# V1.net
KiCad netlist of a schematic drawn in EAGLE
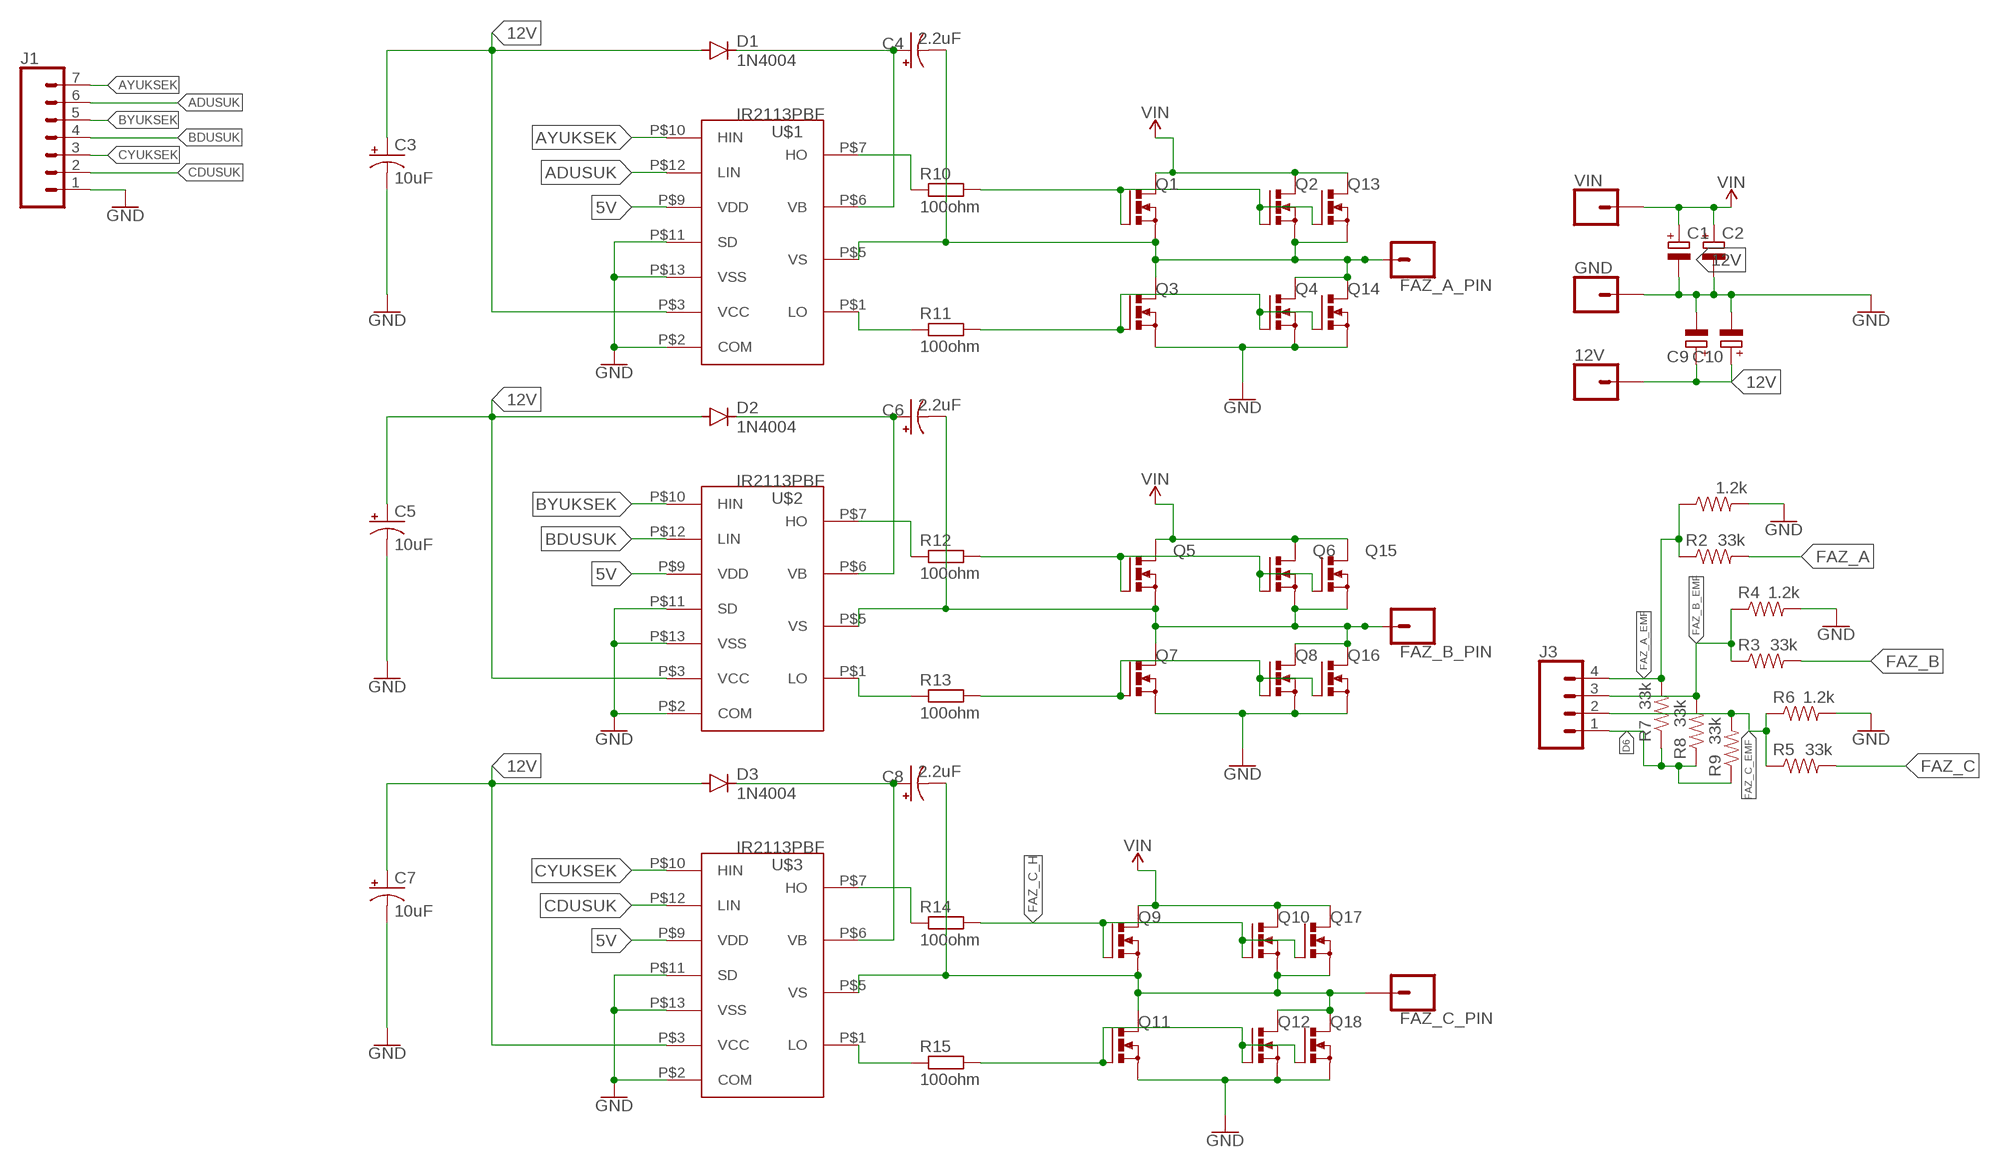
[diagram p0: schematic, sheet 1]

(export (version "E")
  (design (tool "Eeschema 10.0.6"))
  (components
    (comp (ref "12V")
      (value "CONN_01SNAP-MALE")
      (footprint "eagle-import:SNAP-MALE")
      (libsource (lib "eagle-import") (part "CONN_01SNAP-MALE"))
    )
    (comp (ref "C1")
      (value "C-POL_RADIAL-25MM-DIA")
      (footprint "eagle-import:CAPPRD550W110D1250H2500B")
      (libsource (lib "eagle-import") (part "C-POLRADIAL-25MM-DIA_"))
    )
    (comp (ref "C2")
      (value "C-POL_RADIAL-25MM-DIA")
      (footprint "eagle-import:CAPPRD550W110D1250H2500B")
      (libsource (lib "eagle-import") (part "C-POLRADIAL-25MM-DIA_"))
    )
    (comp (ref "C3")
      (value "10uF")
      (footprint "eagle-import:CPOL-RADIAL-2.5MM-5MM")
      (libsource (lib "eagle-import") (part "10UF-POLAR-RADIAL-2.5MM-25V-20%"))
    )
    (comp (ref "C4")
      (value "2.2uF")
      (footprint "eagle-import:CPOL-RADIAL-2.5MM-5MM")
      (libsource (lib "eagle-import") (part "10UF-POLAR-RADIAL-2.5MM-25V-20%"))
    )
    (comp (ref "C5")
      (value "10uF")
      (footprint "eagle-import:CPOL-RADIAL-2.5MM-5MM")
      (libsource (lib "eagle-import") (part "10UF-POLAR-RADIAL-2.5MM-25V-20%"))
    )
    (comp (ref "C6")
      (value "2.2uF")
      (footprint "eagle-import:CPOL-RADIAL-2.5MM-5MM")
      (libsource (lib "eagle-import") (part "10UF-POLAR-RADIAL-2.5MM-25V-20%"))
    )
    (comp (ref "C7")
      (value "10uF")
      (footprint "eagle-import:CPOL-RADIAL-2.5MM-5MM")
      (libsource (lib "eagle-import") (part "10UF-POLAR-RADIAL-2.5MM-25V-20%"))
    )
    (comp (ref "C8")
      (value "2.2uF")
      (footprint "eagle-import:CPOL-RADIAL-2.5MM-5MM")
      (libsource (lib "eagle-import") (part "10UF-POLAR-RADIAL-2.5MM-25V-20%"))
    )
    (comp (ref "C9")
      (value "C-POL_RADIAL-25MM-DIA")
      (footprint "eagle-import:CAPPRD550W110D1250H2500B")
      (libsource (lib "eagle-import") (part "C-POLRADIAL-25MM-DIA_"))
    )
    (comp (ref "C10")
      (value "C-POL_RADIAL-25MM-DIA")
      (footprint "eagle-import:CAPPRD550W110D1250H2500B")
      (libsource (lib "eagle-import") (part "C-POLRADIAL-25MM-DIA_"))
    )
    (comp (ref "D1")
      (value "1N4004")
      (footprint "eagle-import:DO41-10")
      (libsource (lib "eagle-import") (part "1N4004"))
    )
    (comp (ref "D2")
      (value "1N4004")
      (footprint "eagle-import:DO41-10")
      (libsource (lib "eagle-import") (part "1N4004"))
    )
    (comp (ref "D3")
      (value "1N4004")
      (footprint "eagle-import:DO41-10")
      (libsource (lib "eagle-import") (part "1N4004"))
    )
    (comp (ref "FAZ_A_PIN")
      (value "CONN_01SNAP-MALE")
      (footprint "eagle-import:SNAP-MALE")
      (libsource (lib "eagle-import") (part "CONN_01SNAP-MALE"))
    )
    (comp (ref "FAZ_B_PIN")
      (value "CONN_01SNAP-MALE")
      (footprint "eagle-import:SNAP-MALE")
      (libsource (lib "eagle-import") (part "CONN_01SNAP-MALE"))
    )
    (comp (ref "FAZ_C_PIN")
      (value "CONN_01SNAP-MALE")
      (footprint "eagle-import:SNAP-MALE")
      (libsource (lib "eagle-import") (part "CONN_01SNAP-MALE"))
    )
    (comp (ref "GND")
      (value "CONN_01SNAP-MALE")
      (footprint "eagle-import:SNAP-MALE")
      (libsource (lib "eagle-import") (part "CONN_01SNAP-MALE"))
    )
    (comp (ref "J1")
      (value "CONN_07")
      (footprint "eagle-import:1X07")
      (libsource (lib "eagle-import") (part "CONN_07"))
    )
    (comp (ref "J3")
      (value "CONN_04")
      (footprint "eagle-import:1X04")
      (libsource (lib "eagle-import") (part "CONN_04"))
    )
    (comp (ref "Q1")
      (value "PMOSFET_NTO220BV")
      (footprint "eagle-import:TO220BV")
      (libsource (lib "eagle-import") (part "PMOSFET_NTO220BV"))
    )
    (comp (ref "Q2")
      (value "PMOSFET_NTO220BV")
      (footprint "eagle-import:TO220BV")
      (libsource (lib "eagle-import") (part "PMOSFET_NTO220BV"))
    )
    (comp (ref "Q3")
      (value "PMOSFET_NTO220BV")
      (footprint "eagle-import:TO220BV")
      (libsource (lib "eagle-import") (part "PMOSFET_NTO220BV"))
    )
    (comp (ref "Q4")
      (value "PMOSFET_NTO220BV")
      (footprint "eagle-import:TO220BV")
      (libsource (lib "eagle-import") (part "PMOSFET_NTO220BV"))
    )
    (comp (ref "Q5")
      (value "PMOSFET_NTO220BV")
      (footprint "eagle-import:TO220BV")
      (libsource (lib "eagle-import") (part "PMOSFET_NTO220BV"))
    )
    (comp (ref "Q6")
      (value "PMOSFET_NTO220BV")
      (footprint "eagle-import:TO220BV")
      (libsource (lib "eagle-import") (part "PMOSFET_NTO220BV"))
    )
    (comp (ref "Q7")
      (value "PMOSFET_NTO220BV")
      (footprint "eagle-import:TO220BV")
      (libsource (lib "eagle-import") (part "PMOSFET_NTO220BV"))
    )
    (comp (ref "Q8")
      (value "PMOSFET_NTO220BV")
      (footprint "eagle-import:TO220BV")
      (libsource (lib "eagle-import") (part "PMOSFET_NTO220BV"))
    )
    (comp (ref "Q9")
      (value "PMOSFET_NTO220BV")
      (footprint "eagle-import:TO220BV")
      (libsource (lib "eagle-import") (part "PMOSFET_NTO220BV"))
    )
    (comp (ref "Q10")
      (value "PMOSFET_NTO220BV")
      (footprint "eagle-import:TO220BV")
      (libsource (lib "eagle-import") (part "PMOSFET_NTO220BV"))
    )
    (comp (ref "Q11")
      (value "PMOSFET_NTO220BV")
      (footprint "eagle-import:TO220BV")
      (libsource (lib "eagle-import") (part "PMOSFET_NTO220BV"))
    )
    (comp (ref "Q12")
      (value "PMOSFET_NTO220BV")
      (footprint "eagle-import:TO220BV")
      (libsource (lib "eagle-import") (part "PMOSFET_NTO220BV"))
    )
    (comp (ref "Q13")
      (value "PMOSFET_NTO220BV")
      (footprint "eagle-import:TO220BV")
      (libsource (lib "eagle-import") (part "PMOSFET_NTO220BV"))
    )
    (comp (ref "Q14")
      (value "PMOSFET_NTO220BV")
      (footprint "eagle-import:TO220BV")
      (libsource (lib "eagle-import") (part "PMOSFET_NTO220BV"))
    )
    (comp (ref "Q15")
      (value "PMOSFET_NTO220BV")
      (footprint "eagle-import:TO220BV")
      (libsource (lib "eagle-import") (part "PMOSFET_NTO220BV"))
    )
    (comp (ref "Q16")
      (value "PMOSFET_NTO220BV")
      (footprint "eagle-import:TO220BV")
      (libsource (lib "eagle-import") (part "PMOSFET_NTO220BV"))
    )
    (comp (ref "Q17")
      (value "PMOSFET_NTO220BV")
      (footprint "eagle-import:TO220BV")
      (libsource (lib "eagle-import") (part "PMOSFET_NTO220BV"))
    )
    (comp (ref "Q18")
      (value "PMOSFET_NTO220BV")
      (footprint "eagle-import:TO220BV")
      (libsource (lib "eagle-import") (part "PMOSFET_NTO220BV"))
    )
    (comp (ref "R1")
      (value "1.2k")
      (footprint "eagle-import:AXIAL-0.3")
      (libsource (lib "eagle-import") (part "15KOHM-HORIZ-1/4W-5%"))
    )
    (comp (ref "R2")
      (value "33k")
      (footprint "eagle-import:AXIAL-0.3")
      (libsource (lib "eagle-import") (part "15KOHM-HORIZ-1/4W-5%"))
    )
    (comp (ref "R3")
      (value "33k")
      (footprint "eagle-import:AXIAL-0.3")
      (libsource (lib "eagle-import") (part "15KOHM-HORIZ-1/4W-5%"))
    )
    (comp (ref "R4")
      (value "1.2k")
      (footprint "eagle-import:AXIAL-0.3")
      (libsource (lib "eagle-import") (part "15KOHM-HORIZ-1/4W-5%"))
    )
    (comp (ref "R5")
      (value "33k")
      (footprint "eagle-import:AXIAL-0.3")
      (libsource (lib "eagle-import") (part "15KOHM-HORIZ-1/4W-5%"))
    )
    (comp (ref "R6")
      (value "1.2k")
      (footprint "eagle-import:AXIAL-0.3")
      (libsource (lib "eagle-import") (part "15KOHM-HORIZ-1/4W-5%"))
    )
    (comp (ref "R7")
      (value "33k")
      (footprint "eagle-import:AXIAL-0.3")
      (libsource (lib "eagle-import") (part "15KOHM-HORIZ-1/4W-5%"))
    )
    (comp (ref "R8")
      (value "33k")
      (footprint "eagle-import:AXIAL-0.3")
      (libsource (lib "eagle-import") (part "15KOHM-HORIZ-1/4W-5%"))
    )
    (comp (ref "R9")
      (value "33k")
      (footprint "eagle-import:AXIAL-0.3")
      (libsource (lib "eagle-import") (part "15KOHM-HORIZ-1/4W-5%"))
    )
    (comp (ref "R10")
      (value "100ohm")
      (footprint "eagle-import:0207_10")
      (libsource (lib "eagle-import") (part "R-EU_0207/10"))
    )
    (comp (ref "R11")
      (value "100ohm")
      (footprint "eagle-import:0207_10")
      (libsource (lib "eagle-import") (part "R-EU_0207/10"))
    )
    (comp (ref "R12")
      (value "100ohm")
      (footprint "eagle-import:0207_10")
      (libsource (lib "eagle-import") (part "R-EU_0207/10"))
    )
    (comp (ref "R13")
      (value "100ohm")
      (footprint "eagle-import:0207_10")
      (libsource (lib "eagle-import") (part "R-EU_0207/10"))
    )
    (comp (ref "R14")
      (value "100ohm")
      (footprint "eagle-import:0207_10")
      (libsource (lib "eagle-import") (part "R-EU_0207/10"))
    )
    (comp (ref "R15")
      (value "100ohm")
      (footprint "eagle-import:0207_10")
      (libsource (lib "eagle-import") (part "R-EU_0207/10"))
    )
    (comp (ref "U$1")
      (value "IR2113PBF")
      (footprint "eagle-import:PDIP-14")
      (libsource (lib "eagle-import") (part "IR2113PBF"))
    )
    (comp (ref "U$2")
      (value "IR2113PBF")
      (footprint "eagle-import:PDIP-14")
      (libsource (lib "eagle-import") (part "IR2113PBF"))
    )
    (comp (ref "U$3")
      (value "IR2113PBF")
      (footprint "eagle-import:PDIP-14")
      (libsource (lib "eagle-import") (part "IR2113PBF"))
    )
    (comp (ref "VIN")
      (value "CONN_01SNAP-MALE")
      (footprint "eagle-import:SNAP-MALE")
      (libsource (lib "eagle-import") (part "CONN_01SNAP-MALE"))
    )
  )
  (nets
    (net (code "1") (name "5V") (class "Default")
      (node (ref "U$1") (pin "P$9") (pinfunction "VDD_P$9") (pintype "bidirectional"))
      (node (ref "U$2") (pin "P$9") (pinfunction "VDD_P$9") (pintype "bidirectional"))
      (node (ref "U$3") (pin "P$9") (pinfunction "VDD_P$9") (pintype "bidirectional"))
    )
    (net (code "2") (name "12V") (class "Default")
      (node (ref "12V") (pin "2") (pinfunction "1_2") (pintype "passive"))
      (node (ref "C10") (pin "1") (pinfunction "+_1") (pintype "passive"))
      (node (ref "C3") (pin "1") (pinfunction "+_1") (pintype "passive"))
      (node (ref "C5") (pin "1") (pinfunction "+_1") (pintype "passive"))
      (node (ref "C7") (pin "1") (pinfunction "+_1") (pintype "passive"))
      (node (ref "C9") (pin "1") (pinfunction "+_1") (pintype "passive"))
      (node (ref "D1") (pin "A") (pinfunction "A_A") (pintype "passive"))
      (node (ref "D2") (pin "A") (pinfunction "A_A") (pintype "passive"))
      (node (ref "D3") (pin "A") (pinfunction "A_A") (pintype "passive"))
      (node (ref "U$1") (pin "P$3") (pinfunction "VCC_P$3") (pintype "bidirectional"))
      (node (ref "U$2") (pin "P$3") (pinfunction "VCC_P$3") (pintype "bidirectional"))
      (node (ref "U$3") (pin "P$3") (pinfunction "VCC_P$3") (pintype "bidirectional"))
    )
    (net (code "3") (name "ADUSUK") (class "Default")
      (node (ref "J1") (pin "6") (pinfunction "6_6") (pintype "passive"))
      (node (ref "U$1") (pin "P$12") (pinfunction "LIN_P$12") (pintype "bidirectional"))
    )
    (net (code "4") (name "AYUKSEK") (class "Default")
      (node (ref "J1") (pin "7") (pinfunction "7_7") (pintype "passive"))
      (node (ref "U$1") (pin "P$10") (pinfunction "HIN_P$10") (pintype "bidirectional"))
    )
    (net (code "5") (name "BDUSUK") (class "Default")
      (node (ref "J1") (pin "4") (pinfunction "4_4") (pintype "passive"))
      (node (ref "U$2") (pin "P$12") (pinfunction "LIN_P$12") (pintype "bidirectional"))
    )
    (net (code "6") (name "BYUKSEK") (class "Default")
      (node (ref "J1") (pin "5") (pinfunction "5_5") (pintype "passive"))
      (node (ref "U$2") (pin "P$10") (pinfunction "HIN_P$10") (pintype "bidirectional"))
    )
    (net (code "7") (name "CDUSUK") (class "Default")
      (node (ref "J1") (pin "2") (pinfunction "2_2") (pintype "passive"))
      (node (ref "U$3") (pin "P$12") (pinfunction "LIN_P$12") (pintype "bidirectional"))
    )
    (net (code "8") (name "CYUKSEK") (class "Default")
      (node (ref "J1") (pin "3") (pinfunction "3_3") (pintype "passive"))
      (node (ref "U$3") (pin "P$10") (pinfunction "HIN_P$10") (pintype "bidirectional"))
    )
    (net (code "9") (name "D6") (class "Default")
      (node (ref "J3") (pin "1") (pinfunction "1_1") (pintype "passive"))
      (node (ref "R7") (pin "P$1") (pinfunction "1_P$1") (pintype "passive"))
      (node (ref "R8") (pin "P$1") (pinfunction "1_P$1") (pintype "passive"))
      (node (ref "R9") (pin "P$1") (pinfunction "1_P$1") (pintype "passive"))
    )
    (net (code "10") (name "FAZ_A") (class "Default")
      (node (ref "C4") (pin "2") (pinfunction "-_2") (pintype "passive"))
      (node (ref "FAZ_A_PIN") (pin "2") (pinfunction "1_2") (pintype "passive"))
      (node (ref "Q1") (pin "S") (pinfunction "S_S") (pintype "passive"))
      (node (ref "Q13") (pin "S") (pinfunction "S_S") (pintype "passive"))
      (node (ref "Q14") (pin "D") (pinfunction "D_D") (pintype "passive"))
      (node (ref "Q2") (pin "S") (pinfunction "S_S") (pintype "passive"))
      (node (ref "Q3") (pin "D") (pinfunction "D_D") (pintype "passive"))
      (node (ref "Q4") (pin "D") (pinfunction "D_D") (pintype "passive"))
      (node (ref "R2") (pin "P$2") (pinfunction "2_P$2") (pintype "passive"))
      (node (ref "U$1") (pin "P$5") (pinfunction "VS_P$5") (pintype "bidirectional"))
    )
    (net (code "11") (name "FAZ_A_EMF") (class "Default")
      (node (ref "J3") (pin "4") (pinfunction "4_4") (pintype "passive"))
      (node (ref "R1") (pin "P$1") (pinfunction "1_P$1") (pintype "passive"))
      (node (ref "R2") (pin "P$1") (pinfunction "1_P$1") (pintype "passive"))
      (node (ref "R7") (pin "P$2") (pinfunction "2_P$2") (pintype "passive"))
    )
    (net (code "12") (name "FAZ_B") (class "Default")
      (node (ref "C6") (pin "2") (pinfunction "-_2") (pintype "passive"))
      (node (ref "FAZ_B_PIN") (pin "2") (pinfunction "1_2") (pintype "passive"))
      (node (ref "Q15") (pin "S") (pinfunction "S_S") (pintype "passive"))
      (node (ref "Q16") (pin "D") (pinfunction "D_D") (pintype "passive"))
      (node (ref "Q5") (pin "S") (pinfunction "S_S") (pintype "passive"))
      (node (ref "Q6") (pin "S") (pinfunction "S_S") (pintype "passive"))
      (node (ref "Q7") (pin "D") (pinfunction "D_D") (pintype "passive"))
      (node (ref "Q8") (pin "D") (pinfunction "D_D") (pintype "passive"))
      (node (ref "R3") (pin "P$2") (pinfunction "2_P$2") (pintype "passive"))
      (node (ref "U$2") (pin "P$5") (pinfunction "VS_P$5") (pintype "bidirectional"))
    )
    (net (code "13") (name "FAZ_B_EMF") (class "Default")
      (node (ref "J3") (pin "3") (pinfunction "3_3") (pintype "passive"))
      (node (ref "R3") (pin "P$1") (pinfunction "1_P$1") (pintype "passive"))
      (node (ref "R4") (pin "P$1") (pinfunction "1_P$1") (pintype "passive"))
      (node (ref "R8") (pin "P$2") (pinfunction "2_P$2") (pintype "passive"))
    )
    (net (code "14") (name "FAZ_C") (class "Default")
      (node (ref "C8") (pin "2") (pinfunction "-_2") (pintype "passive"))
      (node (ref "FAZ_C_PIN") (pin "2") (pinfunction "1_2") (pintype "passive"))
      (node (ref "Q10") (pin "S") (pinfunction "S_S") (pintype "passive"))
      (node (ref "Q11") (pin "D") (pinfunction "D_D") (pintype "passive"))
      (node (ref "Q12") (pin "D") (pinfunction "D_D") (pintype "passive"))
      (node (ref "Q17") (pin "S") (pinfunction "S_S") (pintype "passive"))
      (node (ref "Q18") (pin "D") (pinfunction "D_D") (pintype "passive"))
      (node (ref "Q9") (pin "S") (pinfunction "S_S") (pintype "passive"))
      (node (ref "R5") (pin "P$2") (pinfunction "2_P$2") (pintype "passive"))
      (node (ref "U$3") (pin "P$5") (pinfunction "VS_P$5") (pintype "bidirectional"))
    )
    (net (code "15") (name "FAZ_C_EMF") (class "Default")
      (node (ref "J3") (pin "2") (pinfunction "2_2") (pintype "passive"))
      (node (ref "R5") (pin "P$1") (pinfunction "1_P$1") (pintype "passive"))
      (node (ref "R6") (pin "P$1") (pinfunction "1_P$1") (pintype "passive"))
      (node (ref "R9") (pin "P$2") (pinfunction "2_P$2") (pintype "passive"))
    )
    (net (code "16") (name "FAZ_C_H") (class "Default")
      (node (ref "Q10") (pin "G") (pinfunction "G_G") (pintype "passive"))
      (node (ref "Q17") (pin "G") (pinfunction "G_G") (pintype "passive"))
      (node (ref "Q9") (pin "G") (pinfunction "G_G") (pintype "passive"))
      (node (ref "R14") (pin "2") (pinfunction "2_2") (pintype "passive"))
    )
    (net (code "17") (name "GND") (class "Default")
      (node (ref "C1") (pin "2") (pinfunction "-_2") (pintype "passive"))
      (node (ref "C10") (pin "2") (pinfunction "-_2") (pintype "passive"))
      (node (ref "C2") (pin "2") (pinfunction "-_2") (pintype "passive"))
      (node (ref "C3") (pin "2") (pinfunction "-_2") (pintype "passive"))
      (node (ref "C5") (pin "2") (pinfunction "-_2") (pintype "passive"))
      (node (ref "C7") (pin "2") (pinfunction "-_2") (pintype "passive"))
      (node (ref "C9") (pin "2") (pinfunction "-_2") (pintype "passive"))
      (node (ref "GND") (pin "2") (pinfunction "1_2") (pintype "passive"))
      (node (ref "J1") (pin "1") (pinfunction "1_1") (pintype "passive"))
      (node (ref "Q11") (pin "S") (pinfunction "S_S") (pintype "passive"))
      (node (ref "Q12") (pin "S") (pinfunction "S_S") (pintype "passive"))
      (node (ref "Q14") (pin "S") (pinfunction "S_S") (pintype "passive"))
      (node (ref "Q16") (pin "S") (pinfunction "S_S") (pintype "passive"))
      (node (ref "Q18") (pin "S") (pinfunction "S_S") (pintype "passive"))
      (node (ref "Q3") (pin "S") (pinfunction "S_S") (pintype "passive"))
      (node (ref "Q4") (pin "S") (pinfunction "S_S") (pintype "passive"))
      (node (ref "Q7") (pin "S") (pinfunction "S_S") (pintype "passive"))
      (node (ref "Q8") (pin "S") (pinfunction "S_S") (pintype "passive"))
      (node (ref "R1") (pin "P$2") (pinfunction "2_P$2") (pintype "passive"))
      (node (ref "R4") (pin "P$2") (pinfunction "2_P$2") (pintype "passive"))
      (node (ref "R6") (pin "P$2") (pinfunction "2_P$2") (pintype "passive"))
      (node (ref "U$1") (pin "P$11") (pinfunction "SD_P$11") (pintype "bidirectional"))
      (node (ref "U$1") (pin "P$13") (pinfunction "VSS_P$13") (pintype "bidirectional"))
      (node (ref "U$1") (pin "P$2") (pinfunction "COM_P$2") (pintype "bidirectional"))
      (node (ref "U$2") (pin "P$11") (pinfunction "SD_P$11") (pintype "bidirectional"))
      (node (ref "U$2") (pin "P$13") (pinfunction "VSS_P$13") (pintype "bidirectional"))
      (node (ref "U$2") (pin "P$2") (pinfunction "COM_P$2") (pintype "bidirectional"))
      (node (ref "U$3") (pin "P$11") (pinfunction "SD_P$11") (pintype "bidirectional"))
      (node (ref "U$3") (pin "P$13") (pinfunction "VSS_P$13") (pintype "bidirectional"))
      (node (ref "U$3") (pin "P$2") (pinfunction "COM_P$2") (pintype "bidirectional"))
    )
    (net (code "18") (name "Net-(C4-+)") (class "Default")
      (node (ref "C4") (pin "1") (pinfunction "+_1") (pintype "passive"))
      (node (ref "D1") (pin "C") (pinfunction "C_C") (pintype "passive"))
      (node (ref "U$1") (pin "P$6") (pinfunction "VB_P$6") (pintype "bidirectional"))
    )
    (net (code "19") (name "Net-(C6-+)") (class "Default")
      (node (ref "C6") (pin "1") (pinfunction "+_1") (pintype "passive"))
      (node (ref "D2") (pin "C") (pinfunction "C_C") (pintype "passive"))
      (node (ref "U$2") (pin "P$6") (pinfunction "VB_P$6") (pintype "bidirectional"))
    )
    (net (code "20") (name "Net-(C8-+)") (class "Default")
      (node (ref "C8") (pin "1") (pinfunction "+_1") (pintype "passive"))
      (node (ref "D3") (pin "C") (pinfunction "C_C") (pintype "passive"))
      (node (ref "U$3") (pin "P$6") (pinfunction "VB_P$6") (pintype "bidirectional"))
    )
    (net (code "21") (name "Net-(Q1-PadG)") (class "Default")
      (node (ref "Q1") (pin "G") (pinfunction "G_G") (pintype "passive"))
      (node (ref "Q13") (pin "G") (pinfunction "G_G") (pintype "passive"))
      (node (ref "Q2") (pin "G") (pinfunction "G_G") (pintype "passive"))
      (node (ref "R10") (pin "2") (pinfunction "2_2") (pintype "passive"))
    )
    (net (code "22") (name "Net-(Q11-PadG)") (class "Default")
      (node (ref "Q11") (pin "G") (pinfunction "G_G") (pintype "passive"))
      (node (ref "Q12") (pin "G") (pinfunction "G_G") (pintype "passive"))
      (node (ref "Q18") (pin "G") (pinfunction "G_G") (pintype "passive"))
      (node (ref "R15") (pin "2") (pinfunction "2_2") (pintype "passive"))
    )
    (net (code "23") (name "Net-(Q14-PadG)") (class "Default")
      (node (ref "Q14") (pin "G") (pinfunction "G_G") (pintype "passive"))
      (node (ref "Q3") (pin "G") (pinfunction "G_G") (pintype "passive"))
      (node (ref "Q4") (pin "G") (pinfunction "G_G") (pintype "passive"))
      (node (ref "R11") (pin "2") (pinfunction "2_2") (pintype "passive"))
    )
    (net (code "24") (name "Net-(Q15-PadG)") (class "Default")
      (node (ref "Q15") (pin "G") (pinfunction "G_G") (pintype "passive"))
      (node (ref "Q5") (pin "G") (pinfunction "G_G") (pintype "passive"))
      (node (ref "Q6") (pin "G") (pinfunction "G_G") (pintype "passive"))
      (node (ref "R12") (pin "2") (pinfunction "2_2") (pintype "passive"))
    )
    (net (code "25") (name "Net-(Q16-PadG)") (class "Default")
      (node (ref "Q16") (pin "G") (pinfunction "G_G") (pintype "passive"))
      (node (ref "Q7") (pin "G") (pinfunction "G_G") (pintype "passive"))
      (node (ref "Q8") (pin "G") (pinfunction "G_G") (pintype "passive"))
      (node (ref "R13") (pin "2") (pinfunction "2_2") (pintype "passive"))
    )
    (net (code "26") (name "Net-(U$1-HO)") (class "Default")
      (node (ref "R10") (pin "1") (pinfunction "1_1") (pintype "passive"))
      (node (ref "U$1") (pin "P$7") (pinfunction "HO_P$7") (pintype "bidirectional"))
    )
    (net (code "27") (name "Net-(U$1-LO)") (class "Default")
      (node (ref "R11") (pin "1") (pinfunction "1_1") (pintype "passive"))
      (node (ref "U$1") (pin "P$1") (pinfunction "LO_P$1") (pintype "bidirectional"))
    )
    (net (code "28") (name "Net-(U$2-HO)") (class "Default")
      (node (ref "R12") (pin "1") (pinfunction "1_1") (pintype "passive"))
      (node (ref "U$2") (pin "P$7") (pinfunction "HO_P$7") (pintype "bidirectional"))
    )
    (net (code "29") (name "Net-(U$2-LO)") (class "Default")
      (node (ref "R13") (pin "1") (pinfunction "1_1") (pintype "passive"))
      (node (ref "U$2") (pin "P$1") (pinfunction "LO_P$1") (pintype "bidirectional"))
    )
    (net (code "30") (name "Net-(U$3-HO)") (class "Default")
      (node (ref "R14") (pin "1") (pinfunction "1_1") (pintype "passive"))
      (node (ref "U$3") (pin "P$7") (pinfunction "HO_P$7") (pintype "bidirectional"))
    )
    (net (code "31") (name "Net-(U$3-LO)") (class "Default")
      (node (ref "R15") (pin "1") (pinfunction "1_1") (pintype "passive"))
      (node (ref "U$3") (pin "P$1") (pinfunction "LO_P$1") (pintype "bidirectional"))
    )
    (net (code "32") (name "VIN") (class "Default")
      (node (ref "C1") (pin "1") (pinfunction "+_1") (pintype "passive"))
      (node (ref "C2") (pin "1") (pinfunction "+_1") (pintype "passive"))
      (node (ref "Q1") (pin "D") (pinfunction "D_D") (pintype "passive"))
      (node (ref "Q10") (pin "D") (pinfunction "D_D") (pintype "passive"))
      (node (ref "Q13") (pin "D") (pinfunction "D_D") (pintype "passive"))
      (node (ref "Q15") (pin "D") (pinfunction "D_D") (pintype "passive"))
      (node (ref "Q17") (pin "D") (pinfunction "D_D") (pintype "passive"))
      (node (ref "Q2") (pin "D") (pinfunction "D_D") (pintype "passive"))
      (node (ref "Q5") (pin "D") (pinfunction "D_D") (pintype "passive"))
      (node (ref "Q6") (pin "D") (pinfunction "D_D") (pintype "passive"))
      (node (ref "Q9") (pin "D") (pinfunction "D_D") (pintype "passive"))
      (node (ref "VIN") (pin "2") (pinfunction "1_2") (pintype "passive"))
    )
  )
)
